# team4-selo-atmega32u4-usb.net
KiCad netlist of a schematic drawn in EAGLE
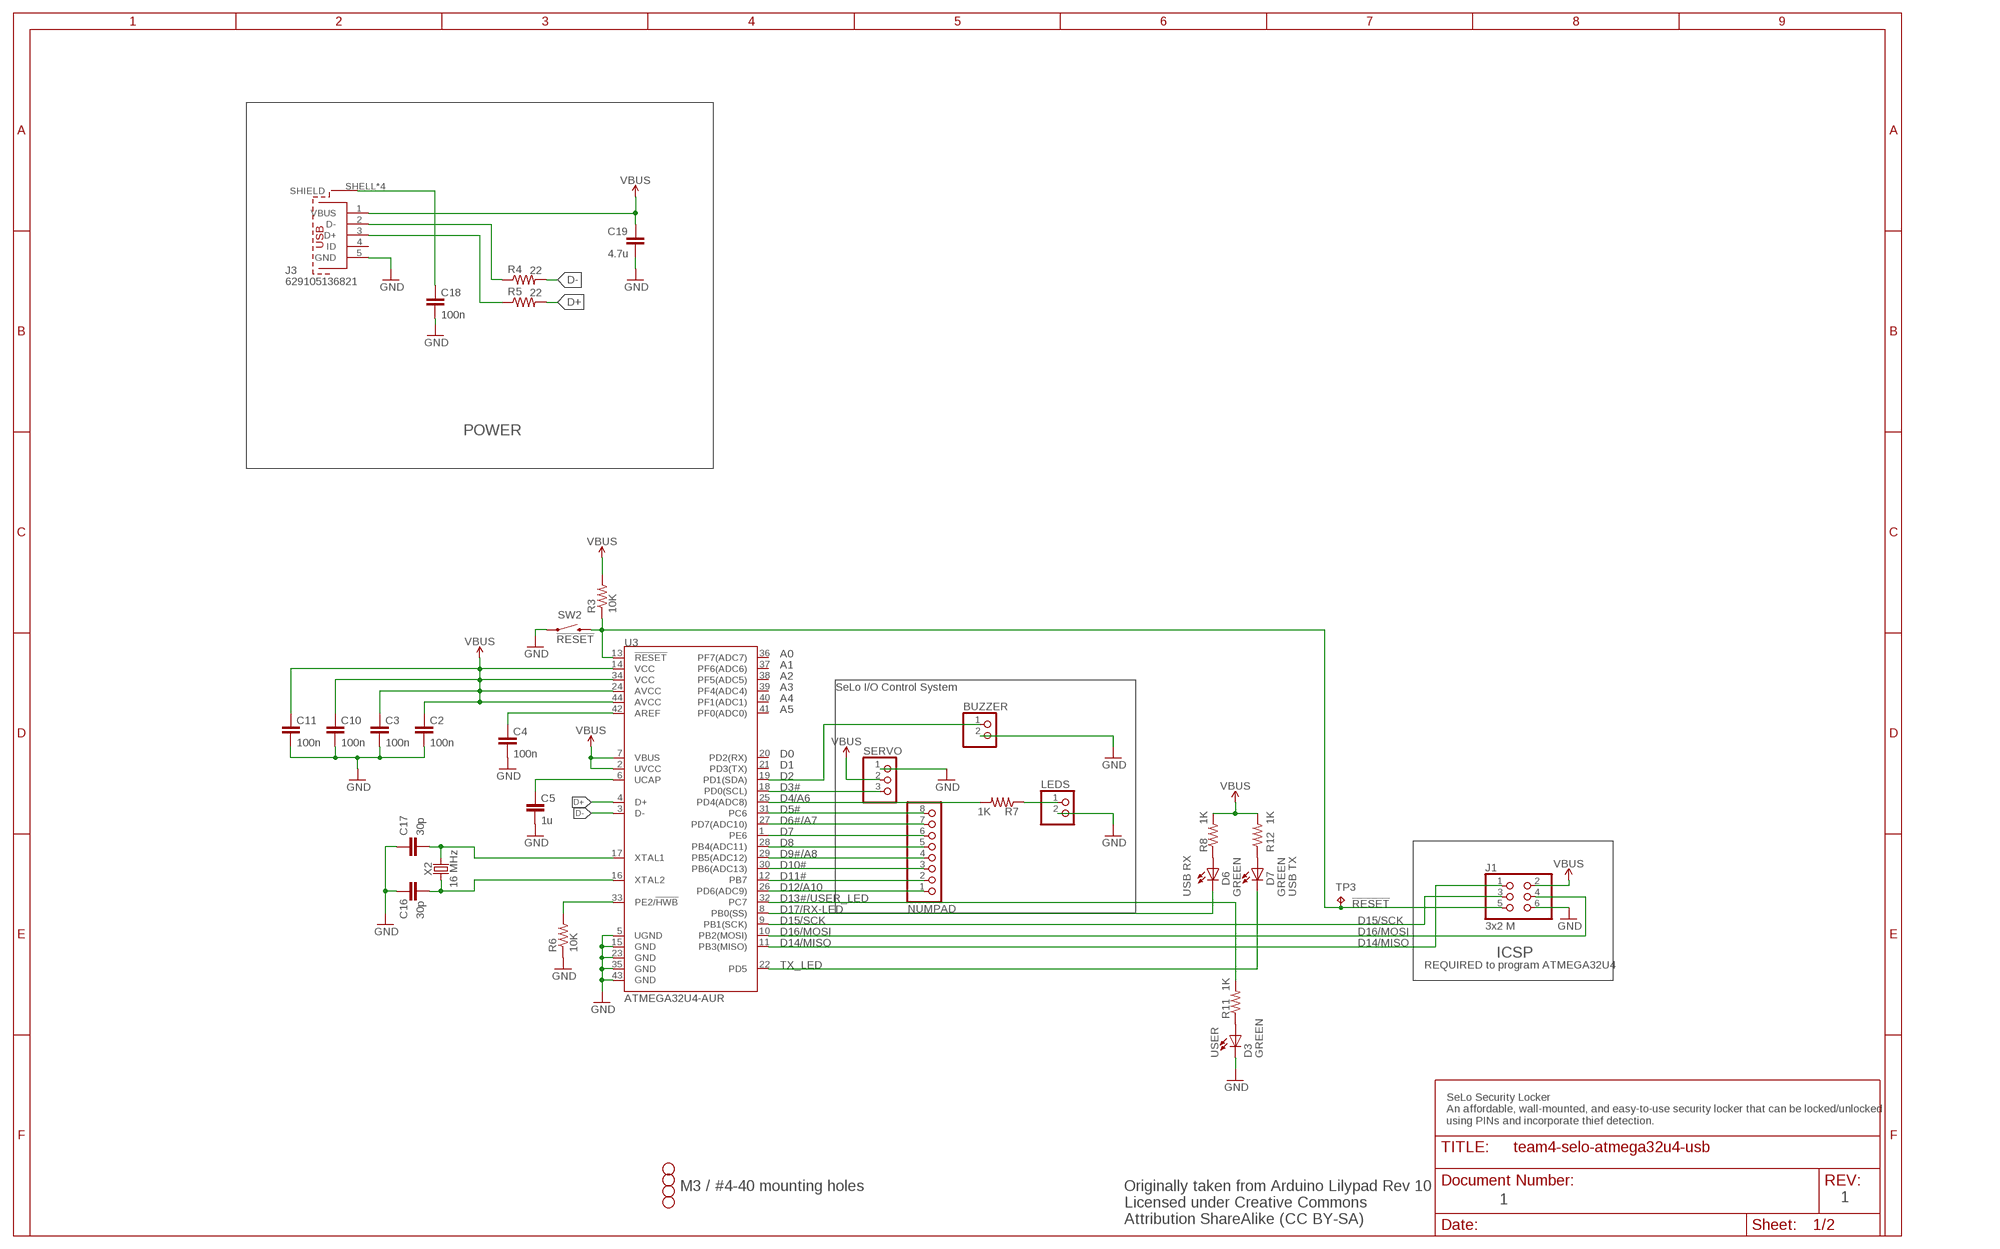
[diagram p0: schematic, sheet 1]

(export (version "E")
  (design (tool "Eeschema 10.0.6"))
  (components
    (comp (ref "BUZZER")
      (value "PINHD-1X2")
      (footprint "eagle-import:1X02")
      (libsource (lib "eagle-import") (part "PINHD-1X2"))
    )
    (comp (ref "C2")
      (value "100n")
      (footprint "eagle-import:C0805K")
      (fields (field (name "MFR") "Samsung") (field (name "MPN") "CL21B104KBCNNNC"))
      (libsource (lib "eagle-import") (part "C-EUC0805K"))
    )
    (comp (ref "C3")
      (value "100n")
      (footprint "eagle-import:C0805K")
      (fields (field (name "MFR") "Samsung") (field (name "MPN") "CL21B104KBCNNNC"))
      (libsource (lib "eagle-import") (part "C-EUC0805K"))
    )
    (comp (ref "C4")
      (value "100n")
      (footprint "eagle-import:C0805K")
      (fields (field (name "MFR") "Samsung") (field (name "MPN") "CL21B104KBCNNNC"))
      (libsource (lib "eagle-import") (part "C-EUC0805K"))
    )
    (comp (ref "C5")
      (value "1u")
      (footprint "eagle-import:C0805K")
      (fields (field (name "MFR") "Samsung") (field (name "MPN") "CL21B105KOFNNNG"))
      (libsource (lib "eagle-import") (part "C-EUC0805K"))
    )
    (comp (ref "C10")
      (value "100n")
      (footprint "eagle-import:C0805K")
      (fields (field (name "MFR") "Samsung") (field (name "MPN") "CL21B104KBCNNNC"))
      (libsource (lib "eagle-import") (part "C-EUC0805K"))
    )
    (comp (ref "C11")
      (value "100n")
      (footprint "eagle-import:C0805K")
      (fields (field (name "MFR") "Samsung") (field (name "MPN") "CL21B104KBCNNNC"))
      (libsource (lib "eagle-import") (part "C-EUC0805K"))
    )
    (comp (ref "C16")
      (value "30p")
      (footprint "eagle-import:C0805K")
      (fields (field (name "MFR") "Samsung") (field (name "MPN") "CL21C300JBANNNC"))
      (libsource (lib "eagle-import") (part "C-EUC0805K"))
    )
    (comp (ref "C17")
      (value "30p")
      (footprint "eagle-import:C0805K")
      (fields (field (name "MFR") "Samsung") (field (name "MPN") "CL21C180JBANNNC"))
      (libsource (lib "eagle-import") (part "C-EUC0805K"))
    )
    (comp (ref "C18")
      (value "100n")
      (footprint "eagle-import:C0805K")
      (fields (field (name "MFR") "Samsung") (field (name "MPN") "CL21B104KBCNNNC"))
      (libsource (lib "eagle-import") (part "C-EUC0805K"))
    )
    (comp (ref "C19")
      (value "4.7u")
      (footprint "eagle-import:C0805K")
      (fields (field (name "MFR") "Samsung") (field (name "MPN") "CL21A475KOFNNNE"))
      (libsource (lib "eagle-import") (part "C-EUC0805K"))
    )
    (comp (ref "D3")
      (value "GREEN")
      (footprint "eagle-import:CHIP-LED0805")
      (fields (field (name "MFR") "Würth Elektronik") (field (name "MPN") "150080GS75000"))
      (libsource (lib "eagle-import") (part "LEDCHIP-LED0805"))
    )
    (comp (ref "D6")
      (value "GREEN")
      (footprint "eagle-import:CHIP-LED0805")
      (fields (field (name "MFR") "Würth Elektronik") (field (name "MPN") "150080GS75000"))
      (libsource (lib "eagle-import") (part "LEDCHIP-LED0805"))
    )
    (comp (ref "D7")
      (value "GREEN")
      (footprint "eagle-import:CHIP-LED0805")
      (fields (field (name "MFR") "Würth Elektronik") (field (name "MPN") "150080GS75000"))
      (libsource (lib "eagle-import") (part "LEDCHIP-LED0805"))
    )
    (comp (ref "H1")
      (value "STAND-OFF")
      (footprint "eagle-import:STAND-OFF")
      (libsource (lib "eagle-import") (part "STAND-OFF"))
    )
    (comp (ref "H2")
      (value "STAND-OFF")
      (footprint "eagle-import:STAND-OFF")
      (libsource (lib "eagle-import") (part "STAND-OFF"))
    )
    (comp (ref "H3")
      (value "STAND-OFF")
      (footprint "eagle-import:STAND-OFF")
      (libsource (lib "eagle-import") (part "STAND-OFF"))
    )
    (comp (ref "H4")
      (value "STAND-OFF")
      (footprint "eagle-import:STAND-OFF")
      (libsource (lib "eagle-import") (part "STAND-OFF"))
    )
    (comp (ref "J1")
      (value "3x2 M")
      (footprint "eagle-import:2X03")
      (fields (field (name "MFR") "Harwin") (field (name "MPN") "M20-9980345"))
      (libsource (lib "eagle-import") (part "PINHD-2X3"))
    )
    (comp (ref "J3")
      (value "629105136821")
      (footprint "eagle-import:629105136821")
      (fields (field (name "MFR") "Wurth"))
      (libsource (lib "eagle-import") (part "629105136821"))
    )
    (comp (ref "LEDS")
      (value "PINHD-1X2")
      (footprint "eagle-import:1X02")
      (libsource (lib "eagle-import") (part "PINHD-1X2"))
    )
    (comp (ref "NUMPAD")
      (value "PINHD-1X8")
      (footprint "eagle-import:1X08")
      (libsource (lib "eagle-import") (part "PINHD-1X8"))
    )
    (comp (ref "R3")
      (value "10K")
      (footprint "eagle-import:R0805")
      (fields (field (name "MFR") "Yageo") (field (name "MPN") "RC0805FR-0710KL"))
      (libsource (lib "eagle-import") (part "R-US_R0805"))
    )
    (comp (ref "R4")
      (value "22")
      (footprint "eagle-import:R0805")
      (fields (field (name "MFR") "Yageo") (field (name "MPN") "RC0805FR-0722RL"))
      (libsource (lib "eagle-import") (part "R-US_R0805"))
    )
    (comp (ref "R5")
      (value "22")
      (footprint "eagle-import:R0805")
      (fields (field (name "MFR") "Yageo") (field (name "MPN") "RC0805FR-0722RL"))
      (libsource (lib "eagle-import") (part "R-US_R0805"))
    )
    (comp (ref "R6")
      (value "10K")
      (footprint "eagle-import:R0805")
      (fields (field (name "MFR") "Yageo") (field (name "MPN") "RC0805FR-0710KL"))
      (libsource (lib "eagle-import") (part "R-US_R0805"))
    )
    (comp (ref "R7")
      (value "1K")
      (footprint "eagle-import:R0805")
      (fields (field (name "MFR") "Yageo") (field (name "MPN") "RC0805FR-071KL"))
      (libsource (lib "eagle-import") (part "R-US_R0805"))
    )
    (comp (ref "R8")
      (value "1K")
      (footprint "eagle-import:R0805")
      (fields (field (name "MFR") "Yageo") (field (name "MPN") "RC0805FR-071KL"))
      (libsource (lib "eagle-import") (part "R-US_R0805"))
    )
    (comp (ref "R11")
      (value "1K")
      (footprint "eagle-import:R0805")
      (fields (field (name "MFR") "Yageo") (field (name "MPN") "RC0805FR-071KL"))
      (libsource (lib "eagle-import") (part "R-US_R0805"))
    )
    (comp (ref "R12")
      (value "1K")
      (footprint "eagle-import:R0805")
      (fields (field (name "MFR") "Yageo") (field (name "MPN") "RC0805FR-071KL"))
      (libsource (lib "eagle-import") (part "R-US_R0805"))
    )
    (comp (ref "SERVO")
      (value "PINHD-1X3")
      (footprint "eagle-import:1X03")
      (libsource (lib "eagle-import") (part "PINHD-1X3"))
    )
    (comp (ref "SW2")
      (value "!RESET")
      (footprint "eagle-import:TACTILE_SWITCH_SMD")
      (fields (field (name "MFR") "C&K") (field (name "MPN") "RS-187R05A2-DS MT RT"))
      (libsource (lib "eagle-import") (part "SWITCH-MOMENTARY-2SMD"))
    )
    (comp (ref "TP3")
      (value "TPPAD1-13")
      (footprint "eagle-import:P1-13")
      (libsource (lib "eagle-import") (part "TPPAD1-13"))
    )
    (comp (ref "U3")
      (value "ATMEGA32U4-AUR")
      (footprint "eagle-import:TQFP44")
      (fields (field (name "MFR") "Microchip") (field (name "PROD_ID") "IC-10828"))
      (libsource (lib "eagle-import") (part "ATMEGA32U4TQFP-44"))
    )
    (comp (ref "X2")
      (value "16 MHz")
      (footprint "eagle-import:HC49UP")
      (fields (field (name "MFR") "ECS") (field (name "MPN") "ECS-160-18-5PX-TR"))
      (libsource (lib "eagle-import") (part "CRYSTALSMD-HC49UP"))
    )
  )
  (nets
    (net (code "1") (name "D+") (class "Default")
      (node (ref "R5") (pin "2") (pinfunction "2_2") (pintype "passive"))
      (node (ref "U3") (pin "4") (pinfunction "D+_4") (pintype "bidirectional"))
    )
    (net (code "2") (name "D-") (class "Default")
      (node (ref "R4") (pin "2") (pinfunction "2_2") (pintype "passive"))
      (node (ref "U3") (pin "3") (pinfunction "D-_3") (pintype "bidirectional"))
    )
    (net (code "3") (name "D13#{slash}USER_LED") (class "Default")
      (node (ref "R11") (pin "2") (pinfunction "2_2") (pintype "passive"))
      (node (ref "U3") (pin "32") (pinfunction "PC7_32") (pintype "bidirectional"))
    )
    (net (code "4") (name "D14{slash}MISO") (class "Default")
      (node (ref "J1") (pin "1") (pinfunction "1_1") (pintype "passive"))
      (node (ref "U3") (pin "11") (pinfunction "PB3(MISO)_11") (pintype "bidirectional"))
    )
    (net (code "5") (name "D15{slash}SCK") (class "Default")
      (node (ref "J1") (pin "3") (pinfunction "3_3") (pintype "passive"))
      (node (ref "U3") (pin "9") (pinfunction "PB1(SCK)_9") (pintype "bidirectional"))
    )
    (net (code "6") (name "D16{slash}MOSI") (class "Default")
      (node (ref "J1") (pin "4") (pinfunction "4_4") (pintype "passive"))
      (node (ref "U3") (pin "10") (pinfunction "PB2(MOSI)_10") (pintype "bidirectional"))
    )
    (net (code "7") (name "D17{slash}RX-LED") (class "Default")
      (node (ref "D6") (pin "C") (pinfunction "C_C") (pintype "passive"))
      (node (ref "U3") (pin "8") (pinfunction "PB0(SS)_8") (pintype "bidirectional"))
    )
    (net (code "8") (name "GND") (class "Default")
      (node (ref "BUZZER") (pin "2") (pinfunction "2_2") (pintype "passive"))
      (node (ref "C10") (pin "2") (pinfunction "2_2") (pintype "passive"))
      (node (ref "C11") (pin "2") (pinfunction "2_2") (pintype "passive"))
      (node (ref "C16") (pin "2") (pinfunction "2_2") (pintype "passive"))
      (node (ref "C17") (pin "2") (pinfunction "2_2") (pintype "passive"))
      (node (ref "C18") (pin "2") (pinfunction "2_2") (pintype "passive"))
      (node (ref "C19") (pin "2") (pinfunction "2_2") (pintype "passive"))
      (node (ref "C2") (pin "2") (pinfunction "2_2") (pintype "passive"))
      (node (ref "C3") (pin "2") (pinfunction "2_2") (pintype "passive"))
      (node (ref "C4") (pin "2") (pinfunction "2_2") (pintype "passive"))
      (node (ref "C5") (pin "2") (pinfunction "2_2") (pintype "passive"))
      (node (ref "D3") (pin "C") (pinfunction "C_C") (pintype "passive"))
      (node (ref "J1") (pin "6") (pinfunction "6_6") (pintype "passive"))
      (node (ref "J3") (pin "5") (pinfunction "GND_5") (pintype "passive"))
      (node (ref "LEDS") (pin "2") (pinfunction "2_2") (pintype "passive"))
      (node (ref "R6") (pin "1") (pinfunction "1_1") (pintype "passive"))
      (node (ref "SERVO") (pin "1") (pinfunction "1_1") (pintype "passive"))
      (node (ref "SW2") (pin "1") (pinfunction "1_1") (pintype "passive"))
      (node (ref "U3") (pin "15") (pinfunction "GND_15") (pintype "bidirectional"))
      (node (ref "U3") (pin "23") (pinfunction "GND_23") (pintype "bidirectional"))
      (node (ref "U3") (pin "35") (pinfunction "GND_35") (pintype "bidirectional"))
      (node (ref "U3") (pin "43") (pinfunction "GND_43") (pintype "bidirectional"))
      (node (ref "U3") (pin "5") (pinfunction "UGND_5") (pintype "bidirectional"))
    )
    (net (code "9") (name "Net-(C18-Pad1)") (class "Default")
      (node (ref "C18") (pin "1") (pinfunction "1_1") (pintype "passive"))
      (node (ref "J3") (pin "SHELL") (pinfunction "SHIELD_SHELL") (pintype "passive"))
      (node (ref "J3") (pin "SHELL1") (pinfunction "SHIELD_SHELL1") (pintype "passive"))
      (node (ref "J3") (pin "SHELL2") (pinfunction "SHIELD_SHELL2") (pintype "passive"))
      (node (ref "J3") (pin "SHELL3") (pinfunction "SHIELD_SHELL3") (pintype "passive"))
    )
    (net (code "10") (name "Net-(D3-PadA)") (class "Default")
      (node (ref "D3") (pin "A") (pinfunction "A_A") (pintype "passive"))
      (node (ref "R11") (pin "1") (pinfunction "1_1") (pintype "passive"))
    )
    (net (code "11") (name "Net-(D6-PadA)") (class "Default")
      (node (ref "D6") (pin "A") (pinfunction "A_A") (pintype "passive"))
      (node (ref "R8") (pin "1") (pinfunction "1_1") (pintype "passive"))
    )
    (net (code "12") (name "Net-(D7-PadA)") (class "Default")
      (node (ref "D7") (pin "A") (pinfunction "A_A") (pintype "passive"))
      (node (ref "R12") (pin "1") (pinfunction "1_1") (pintype "passive"))
    )
    (net (code "13") (name "Net-(J3-D+)") (class "Default")
      (node (ref "J3") (pin "3") (pinfunction "D+_3") (pintype "passive"))
      (node (ref "R5") (pin "1") (pinfunction "1_1") (pintype "passive"))
    )
    (net (code "14") (name "Net-(J3-D-)") (class "Default")
      (node (ref "J3") (pin "2") (pinfunction "D-_2") (pintype "passive"))
      (node (ref "R4") (pin "1") (pinfunction "1_1") (pintype "passive"))
    )
    (net (code "15") (name "Net-(LEDS-Pad1)") (class "Default")
      (node (ref "LEDS") (pin "1") (pinfunction "1_1") (pintype "passive"))
      (node (ref "R7") (pin "1") (pinfunction "1_1") (pintype "passive"))
    )
    (net (code "16") (name "Net-(U3-AREF)") (class "Default")
      (node (ref "C4") (pin "1") (pinfunction "1_1") (pintype "passive"))
      (node (ref "U3") (pin "42") (pinfunction "AREF_42") (pintype "bidirectional"))
    )
    (net (code "17") (name "Net-(U3-PB4(ADC11))") (class "Default")
      (node (ref "NUMPAD") (pin "5") (pinfunction "5_5") (pintype "passive"))
      (node (ref "U3") (pin "28") (pinfunction "PB4(ADC11)_28") (pintype "bidirectional"))
    )
    (net (code "18") (name "Net-(U3-PB5(ADC12))") (class "Default")
      (node (ref "NUMPAD") (pin "4") (pinfunction "4_4") (pintype "passive"))
      (node (ref "U3") (pin "29") (pinfunction "PB5(ADC12)_29") (pintype "bidirectional"))
    )
    (net (code "19") (name "Net-(U3-PB6(ADC13))") (class "Default")
      (node (ref "NUMPAD") (pin "3") (pinfunction "3_3") (pintype "passive"))
      (node (ref "U3") (pin "30") (pinfunction "PB6(ADC13)_30") (pintype "bidirectional"))
    )
    (net (code "20") (name "Net-(U3-PB7)") (class "Default")
      (node (ref "NUMPAD") (pin "2") (pinfunction "2_2") (pintype "passive"))
      (node (ref "U3") (pin "12") (pinfunction "PB7_12") (pintype "bidirectional"))
    )
    (net (code "21") (name "Net-(U3-PC6)") (class "Default")
      (node (ref "NUMPAD") (pin "8") (pinfunction "8_8") (pintype "passive"))
      (node (ref "U3") (pin "31") (pinfunction "PC6_31") (pintype "bidirectional"))
    )
    (net (code "22") (name "Net-(U3-PD0(SCL))") (class "Default")
      (node (ref "SERVO") (pin "3") (pinfunction "3_3") (pintype "passive"))
      (node (ref "U3") (pin "18") (pinfunction "PD0(SCL)_18") (pintype "bidirectional"))
    )
    (net (code "23") (name "Net-(U3-PD1(SDA))") (class "Default")
      (node (ref "BUZZER") (pin "1") (pinfunction "1_1") (pintype "passive"))
      (node (ref "U3") (pin "19") (pinfunction "PD1(SDA)_19") (pintype "bidirectional"))
    )
    (net (code "24") (name "Net-(U3-PD4(ADC8))") (class "Default")
      (node (ref "R7") (pin "2") (pinfunction "2_2") (pintype "passive"))
      (node (ref "U3") (pin "25") (pinfunction "PD4(ADC8)_25") (pintype "bidirectional"))
    )
    (net (code "25") (name "Net-(U3-PD6(ADC9))") (class "Default")
      (node (ref "NUMPAD") (pin "1") (pinfunction "1_1") (pintype "passive"))
      (node (ref "U3") (pin "26") (pinfunction "PD6(ADC9)_26") (pintype "bidirectional"))
    )
    (net (code "26") (name "Net-(U3-PD7(ADC10))") (class "Default")
      (node (ref "NUMPAD") (pin "7") (pinfunction "7_7") (pintype "passive"))
      (node (ref "U3") (pin "27") (pinfunction "PD7(ADC10)_27") (pintype "bidirectional"))
    )
    (net (code "27") (name "Net-(U3-PE2{slash}~{HWB})") (class "Default")
      (node (ref "R6") (pin "2") (pinfunction "2_2") (pintype "passive"))
      (node (ref "U3") (pin "33") (pinfunction "PE2/~{HWB}_33") (pintype "bidirectional"))
    )
    (net (code "28") (name "Net-(U3-PE6)") (class "Default")
      (node (ref "NUMPAD") (pin "6") (pinfunction "6_6") (pintype "passive"))
      (node (ref "U3") (pin "1") (pinfunction "PE6_1") (pintype "bidirectional"))
    )
    (net (code "29") (name "Net-(U3-UCAP)") (class "Default")
      (node (ref "C5") (pin "1") (pinfunction "1_1") (pintype "passive"))
      (node (ref "U3") (pin "6") (pinfunction "UCAP_6") (pintype "bidirectional"))
    )
    (net (code "30") (name "Net-(U3-XTAL1)") (class "Default")
      (node (ref "C17") (pin "1") (pinfunction "1_1") (pintype "passive"))
      (node (ref "U3") (pin "17") (pinfunction "XTAL1_17") (pintype "bidirectional"))
      (node (ref "X2") (pin "2") (pinfunction "2_2") (pintype "passive"))
    )
    (net (code "31") (name "Net-(U3-XTAL2)") (class "Default")
      (node (ref "C16") (pin "1") (pinfunction "1_1") (pintype "passive"))
      (node (ref "U3") (pin "16") (pinfunction "XTAL2_16") (pintype "bidirectional"))
      (node (ref "X2") (pin "1") (pinfunction "1_1") (pintype "passive"))
    )
    (net (code "32") (name "TX_LED") (class "Default")
      (node (ref "D7") (pin "C") (pinfunction "C_C") (pintype "passive"))
      (node (ref "U3") (pin "22") (pinfunction "PD5_22") (pintype "bidirectional"))
    )
    (net (code "33") (name "VBUS") (class "Default")
      (node (ref "C10") (pin "1") (pinfunction "1_1") (pintype "passive"))
      (node (ref "C11") (pin "1") (pinfunction "1_1") (pintype "passive"))
      (node (ref "C19") (pin "1") (pinfunction "1_1") (pintype "passive"))
      (node (ref "C2") (pin "1") (pinfunction "1_1") (pintype "passive"))
      (node (ref "C3") (pin "1") (pinfunction "1_1") (pintype "passive"))
      (node (ref "J1") (pin "2") (pinfunction "2_2") (pintype "passive"))
      (node (ref "J3") (pin "1") (pinfunction "VBUS_1") (pintype "passive"))
      (node (ref "R12") (pin "2") (pinfunction "2_2") (pintype "passive"))
      (node (ref "R3") (pin "2") (pinfunction "2_2") (pintype "passive"))
      (node (ref "R8") (pin "2") (pinfunction "2_2") (pintype "passive"))
      (node (ref "SERVO") (pin "2") (pinfunction "2_2") (pintype "passive"))
      (node (ref "U3") (pin "14") (pinfunction "VCC_14") (pintype "bidirectional"))
      (node (ref "U3") (pin "2") (pinfunction "UVCC_2") (pintype "bidirectional"))
      (node (ref "U3") (pin "24") (pinfunction "AVCC_24") (pintype "bidirectional"))
      (node (ref "U3") (pin "34") (pinfunction "VCC_34") (pintype "bidirectional"))
      (node (ref "U3") (pin "44") (pinfunction "AVCC_44") (pintype "bidirectional"))
      (node (ref "U3") (pin "7") (pinfunction "VBUS_7") (pintype "bidirectional"))
    )
    (net (code "34") (name "unconnected-(J3-ID-Pad4)") (class "Default")
      (node (ref "J3") (pin "4") (pinfunction "ID_4") (pintype "passive"))
    )
    (net (code "35") (name "unconnected-(U3-PD2(RX)-Pad20)") (class "Default")
      (node (ref "U3") (pin "20") (pinfunction "PD2(RX)_20") (pintype "bidirectional"))
    )
    (net (code "36") (name "unconnected-(U3-PD3(TX)-Pad21)") (class "Default")
      (node (ref "U3") (pin "21") (pinfunction "PD3(TX)_21") (pintype "bidirectional"))
    )
    (net (code "37") (name "unconnected-(U3-PF0(ADC0)-Pad41)") (class "Default")
      (node (ref "U3") (pin "41") (pinfunction "PF0(ADC0)_41") (pintype "bidirectional"))
    )
    (net (code "38") (name "unconnected-(U3-PF1(ADC1)-Pad40)") (class "Default")
      (node (ref "U3") (pin "40") (pinfunction "PF1(ADC1)_40") (pintype "bidirectional"))
    )
    (net (code "39") (name "unconnected-(U3-PF4(ADC4)-Pad39)") (class "Default")
      (node (ref "U3") (pin "39") (pinfunction "PF4(ADC4)_39") (pintype "bidirectional"))
    )
    (net (code "40") (name "unconnected-(U3-PF5(ADC5)-Pad38)") (class "Default")
      (node (ref "U3") (pin "38") (pinfunction "PF5(ADC5)_38") (pintype "bidirectional"))
    )
    (net (code "41") (name "unconnected-(U3-PF6(ADC6)-Pad37)") (class "Default")
      (node (ref "U3") (pin "37") (pinfunction "PF6(ADC6)_37") (pintype "bidirectional"))
    )
    (net (code "42") (name "unconnected-(U3-PF7(ADC7)-Pad36)") (class "Default")
      (node (ref "U3") (pin "36") (pinfunction "PF7(ADC7)_36") (pintype "bidirectional"))
    )
    (net (code "43") (name "~{RESET}") (class "Default")
      (node (ref "J1") (pin "5") (pinfunction "5_5") (pintype "passive"))
      (node (ref "R3") (pin "1") (pinfunction "1_1") (pintype "passive"))
      (node (ref "SW2") (pin "3") (pinfunction "2_3") (pintype "passive"))
      (node (ref "TP3") (pin "TP") (pinfunction "TP_TP") (pintype "input"))
      (node (ref "U3") (pin "13") (pinfunction "~{RESET}_13") (pintype "bidirectional"))
    )
  )
)
